# syspcb.net
KiCad netlist of a schematic drawn in Altium Designer
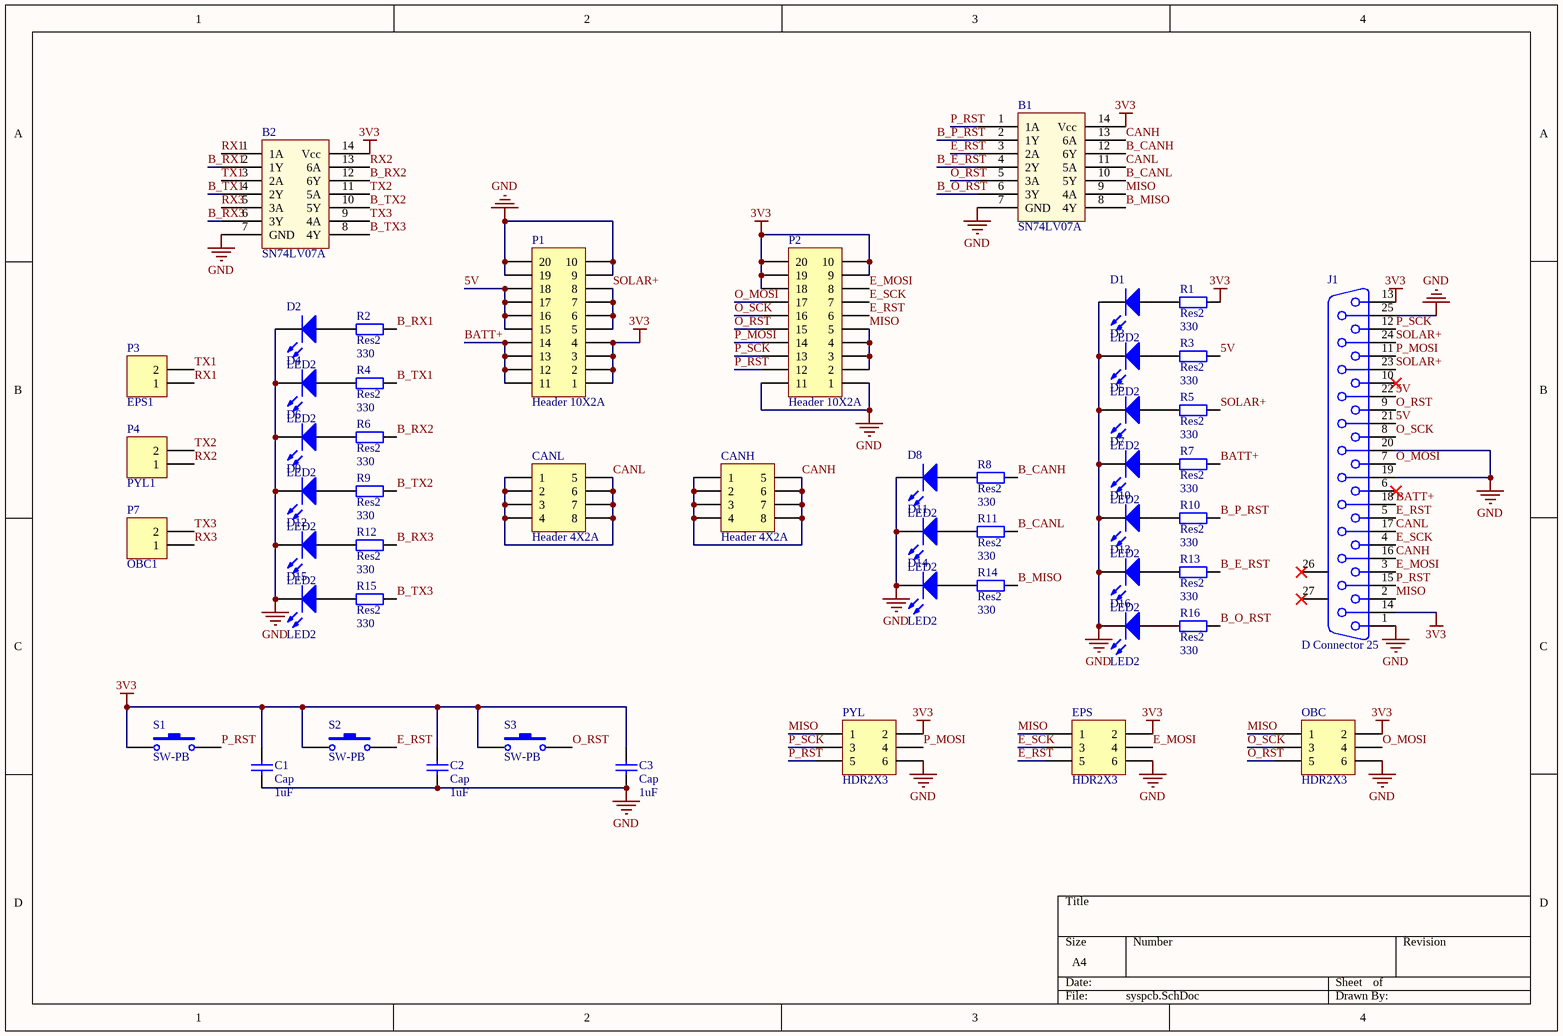
[diagram p0: syspcb.SchDoc]

(export (version "E")
  (design (tool "Eeschema 10.0.6"))
  (components
    (comp (ref "B1")
      (value "SN74LV07A")
      (footprint "SOIC127P600X175-14N")
      (libsource (lib "CUSTOM") (part "SN74LV07A"))
    )
    (comp (ref "B2")
      (value "SN74LV07A")
      (footprint "SOIC127P600X175-14N")
      (libsource (lib "CUSTOM") (part "SN74LV07A"))
    )
    (comp (ref "C1")
      (value "Cap")
      (footprint "1608[0603]")
      (description "Capacitor")
      (fields (field (name "ALTIUM_VALUE") "1uF") (field (name "PUBLISHER") "Altium Limited"))
      (libsource (lib "Miscellaneous Devices") (part "Cap"))
    )
    (comp (ref "C2")
      (value "Cap")
      (footprint "1608[0603]")
      (description "Capacitor")
      (fields (field (name "ALTIUM_VALUE") "1uF") (field (name "PUBLISHER") "Altium Limited"))
      (libsource (lib "Miscellaneous Devices") (part "Cap"))
    )
    (comp (ref "C3")
      (value "Cap")
      (footprint "1608[0603]")
      (description "Capacitor")
      (fields (field (name "ALTIUM_VALUE") "1uF") (field (name "PUBLISHER") "Altium Limited"))
      (libsource (lib "Miscellaneous Devices") (part "Cap"))
    )
    (comp (ref "CANH")
      (value "Header 4X2A")
      (footprint "HDR2X4_CEN")
      (description "Header, 4-Pin, Dual row")
      (fields (field (name "PUBLISHER") "Altium Limited"))
      (libsource (lib "Miscellaneous Connectors") (part "Header 4X2A"))
    )
    (comp (ref "CANL")
      (value "Header 4X2A")
      (footprint "HDR2X4_CEN")
      (description "Header, 4-Pin, Dual row")
      (fields (field (name "PUBLISHER") "Altium Limited"))
      (libsource (lib "Miscellaneous Connectors") (part "Header 4X2A"))
    )
    (comp (ref "D1")
      (value "LED2")
      (footprint "0603-LED")
      (description "Typical RED, GREEN, YELLOW, AMBER GaAs LED")
      (fields (field (name "PUBLISHER") "Altium Limited"))
      (libsource (lib "Miscellaneous Devices") (part "LED2"))
    )
    (comp (ref "D2")
      (value "LED2")
      (footprint "0603-LED")
      (description "Typical RED, GREEN, YELLOW, AMBER GaAs LED")
      (fields (field (name "PUBLISHER") "Altium Limited"))
      (libsource (lib "Miscellaneous Devices") (part "LED2"))
    )
    (comp (ref "D3")
      (value "LED2")
      (footprint "0603-LED")
      (description "Typical RED, GREEN, YELLOW, AMBER GaAs LED")
      (fields (field (name "PUBLISHER") "Altium Limited"))
      (libsource (lib "Miscellaneous Devices") (part "LED2"))
    )
    (comp (ref "D4")
      (value "LED2")
      (footprint "0603-LED")
      (description "Typical RED, GREEN, YELLOW, AMBER GaAs LED")
      (fields (field (name "PUBLISHER") "Altium Limited"))
      (libsource (lib "Miscellaneous Devices") (part "LED2"))
    )
    (comp (ref "D5")
      (value "LED2")
      (footprint "0603-LED")
      (description "Typical RED, GREEN, YELLOW, AMBER GaAs LED")
      (fields (field (name "PUBLISHER") "Altium Limited"))
      (libsource (lib "Miscellaneous Devices") (part "LED2"))
    )
    (comp (ref "D6")
      (value "LED2")
      (footprint "0603-LED")
      (description "Typical RED, GREEN, YELLOW, AMBER GaAs LED")
      (fields (field (name "PUBLISHER") "Altium Limited"))
      (libsource (lib "Miscellaneous Devices") (part "LED2"))
    )
    (comp (ref "D7")
      (value "LED2")
      (footprint "0603-LED")
      (description "Typical RED, GREEN, YELLOW, AMBER GaAs LED")
      (fields (field (name "PUBLISHER") "Altium Limited"))
      (libsource (lib "Miscellaneous Devices") (part "LED2"))
    )
    (comp (ref "D8")
      (value "LED2")
      (footprint "0603-LED")
      (description "Typical RED, GREEN, YELLOW, AMBER GaAs LED")
      (fields (field (name "PUBLISHER") "Altium Limited"))
      (libsource (lib "Miscellaneous Devices") (part "LED2"))
    )
    (comp (ref "D9")
      (value "LED2")
      (footprint "0603-LED")
      (description "Typical RED, GREEN, YELLOW, AMBER GaAs LED")
      (fields (field (name "PUBLISHER") "Altium Limited"))
      (libsource (lib "Miscellaneous Devices") (part "LED2"))
    )
    (comp (ref "D10")
      (value "LED2")
      (footprint "0603-LED")
      (description "Typical RED, GREEN, YELLOW, AMBER GaAs LED")
      (fields (field (name "PUBLISHER") "Altium Limited"))
      (libsource (lib "Miscellaneous Devices") (part "LED2"))
    )
    (comp (ref "D11")
      (value "LED2")
      (footprint "0603-LED")
      (description "Typical RED, GREEN, YELLOW, AMBER GaAs LED")
      (fields (field (name "PUBLISHER") "Altium Limited"))
      (libsource (lib "Miscellaneous Devices") (part "LED2"))
    )
    (comp (ref "D12")
      (value "LED2")
      (footprint "0603-LED")
      (description "Typical RED, GREEN, YELLOW, AMBER GaAs LED")
      (fields (field (name "PUBLISHER") "Altium Limited"))
      (libsource (lib "Miscellaneous Devices") (part "LED2"))
    )
    (comp (ref "D13")
      (value "LED2")
      (footprint "0603-LED")
      (description "Typical RED, GREEN, YELLOW, AMBER GaAs LED")
      (fields (field (name "PUBLISHER") "Altium Limited"))
      (libsource (lib "Miscellaneous Devices") (part "LED2"))
    )
    (comp (ref "D14")
      (value "LED2")
      (footprint "0603-LED")
      (description "Typical RED, GREEN, YELLOW, AMBER GaAs LED")
      (fields (field (name "PUBLISHER") "Altium Limited"))
      (libsource (lib "Miscellaneous Devices") (part "LED2"))
    )
    (comp (ref "D15")
      (value "LED2")
      (footprint "0603-LED")
      (description "Typical RED, GREEN, YELLOW, AMBER GaAs LED")
      (fields (field (name "PUBLISHER") "Altium Limited"))
      (libsource (lib "Miscellaneous Devices") (part "LED2"))
    )
    (comp (ref "D16")
      (value "LED2")
      (footprint "0603-LED")
      (description "Typical RED, GREEN, YELLOW, AMBER GaAs LED")
      (fields (field (name "PUBLISHER") "Altium Limited"))
      (libsource (lib "Miscellaneous Devices") (part "LED2"))
    )
    (comp (ref "EPS")
      (value "HDR2X3")
      (footprint "HDR2X3")
      (description "Header, 3-Pin, Dual row")
      (fields (field (name "PUBLISHER") "Altium Limited"))
      (libsource (lib "Miscellaneous Connectors") (part "MHDR2X3"))
    )
    (comp (ref "J1")
      (value "D Connector 25")
      (footprint "DSUB1.385-2H25A")
      (description "Receptacle Assembly, 25 Position, Right Angle")
      (fields (field (name "PUBLISHER") "Altium Limited"))
      (libsource (lib "Miscellaneous Connectors") (part "D Connector 25"))
    )
    (comp (ref "OBC")
      (value "HDR2X3")
      (footprint "HDR2X3")
      (description "Header, 3-Pin, Dual row")
      (fields (field (name "PUBLISHER") "Altium Limited"))
      (libsource (lib "Miscellaneous Connectors") (part "MHDR2X3"))
    )
    (comp (ref "P1")
      (value "Header 10X2A")
      (footprint "HDR2X10_CEN")
      (description "Header, 10-Pin, Dual row")
      (fields (field (name "PUBLISHER") "Altium Limited"))
      (libsource (lib "Miscellaneous Connectors") (part "Header 10X2A"))
    )
    (comp (ref "P2")
      (value "Header 10X2A")
      (footprint "HDR2X10_CEN")
      (description "Header, 10-Pin, Dual row")
      (fields (field (name "PUBLISHER") "Altium Limited"))
      (libsource (lib "Miscellaneous Connectors") (part "Header 10X2A"))
    )
    (comp (ref "P3")
      (value "EPS1")
      (footprint "HDR1X2")
      (description "Header, 2-Pin")
      (fields (field (name "PUBLISHER") "Altium Limited"))
      (libsource (lib "Miscellaneous Connectors") (part "Header 2"))
    )
    (comp (ref "P4")
      (value "PYL1")
      (footprint "HDR1X2")
      (description "Header, 2-Pin")
      (fields (field (name "PUBLISHER") "Altium Limited"))
      (libsource (lib "Miscellaneous Connectors") (part "Header 2"))
    )
    (comp (ref "P7")
      (value "OBC1")
      (footprint "HDR1X2")
      (description "Header, 2-Pin")
      (fields (field (name "PUBLISHER") "Altium Limited"))
      (libsource (lib "Miscellaneous Connectors") (part "Header 2"))
    )
    (comp (ref "PYL")
      (value "HDR2X3")
      (footprint "HDR2X3")
      (description "Header, 3-Pin, Dual row")
      (fields (field (name "PUBLISHER") "Altium Limited"))
      (libsource (lib "Miscellaneous Connectors") (part "MHDR2X3"))
    )
    (comp (ref "R1")
      (value "Res2")
      (footprint "J1-0603")
      (description "Resistor")
      (fields (field (name "ALTIUM_VALUE") "330") (field (name "PUBLISHER") "Altium Limited"))
      (libsource (lib "Miscellaneous Devices") (part "Res2"))
    )
    (comp (ref "R2")
      (value "Res2")
      (footprint "J1-0603")
      (description "Resistor")
      (fields (field (name "ALTIUM_VALUE") "330") (field (name "PUBLISHER") "Altium Limited"))
      (libsource (lib "Miscellaneous Devices") (part "Res2"))
    )
    (comp (ref "R3")
      (value "Res2")
      (footprint "J1-0603")
      (description "Resistor")
      (fields (field (name "ALTIUM_VALUE") "330") (field (name "PUBLISHER") "Altium Limited"))
      (libsource (lib "Miscellaneous Devices") (part "Res2"))
    )
    (comp (ref "R4")
      (value "Res2")
      (footprint "J1-0603")
      (description "Resistor")
      (fields (field (name "ALTIUM_VALUE") "330") (field (name "PUBLISHER") "Altium Limited"))
      (libsource (lib "Miscellaneous Devices") (part "Res2"))
    )
    (comp (ref "R5")
      (value "Res2")
      (footprint "J1-0603")
      (description "Resistor")
      (fields (field (name "ALTIUM_VALUE") "330") (field (name "PUBLISHER") "Altium Limited"))
      (libsource (lib "Miscellaneous Devices") (part "Res2"))
    )
    (comp (ref "R6")
      (value "Res2")
      (footprint "J1-0603")
      (description "Resistor")
      (fields (field (name "ALTIUM_VALUE") "330") (field (name "PUBLISHER") "Altium Limited"))
      (libsource (lib "Miscellaneous Devices") (part "Res2"))
    )
    (comp (ref "R7")
      (value "Res2")
      (footprint "J1-0603")
      (description "Resistor")
      (fields (field (name "ALTIUM_VALUE") "330") (field (name "PUBLISHER") "Altium Limited"))
      (libsource (lib "Miscellaneous Devices") (part "Res2"))
    )
    (comp (ref "R8")
      (value "Res2")
      (footprint "J1-0603")
      (description "Resistor")
      (fields (field (name "ALTIUM_VALUE") "330") (field (name "PUBLISHER") "Altium Limited"))
      (libsource (lib "Miscellaneous Devices") (part "Res2"))
    )
    (comp (ref "R9")
      (value "Res2")
      (footprint "J1-0603")
      (description "Resistor")
      (fields (field (name "ALTIUM_VALUE") "330") (field (name "PUBLISHER") "Altium Limited"))
      (libsource (lib "Miscellaneous Devices") (part "Res2"))
    )
    (comp (ref "R10")
      (value "Res2")
      (footprint "J1-0603")
      (description "Resistor")
      (fields (field (name "ALTIUM_VALUE") "330") (field (name "PUBLISHER") "Altium Limited"))
      (libsource (lib "Miscellaneous Devices") (part "Res2"))
    )
    (comp (ref "R11")
      (value "Res2")
      (footprint "J1-0603")
      (description "Resistor")
      (fields (field (name "ALTIUM_VALUE") "330") (field (name "PUBLISHER") "Altium Limited"))
      (libsource (lib "Miscellaneous Devices") (part "Res2"))
    )
    (comp (ref "R12")
      (value "Res2")
      (footprint "J1-0603")
      (description "Resistor")
      (fields (field (name "ALTIUM_VALUE") "330") (field (name "PUBLISHER") "Altium Limited"))
      (libsource (lib "Miscellaneous Devices") (part "Res2"))
    )
    (comp (ref "R13")
      (value "Res2")
      (footprint "J1-0603")
      (description "Resistor")
      (fields (field (name "ALTIUM_VALUE") "330") (field (name "PUBLISHER") "Altium Limited"))
      (libsource (lib "Miscellaneous Devices") (part "Res2"))
    )
    (comp (ref "R14")
      (value "Res2")
      (footprint "J1-0603")
      (description "Resistor")
      (fields (field (name "ALTIUM_VALUE") "330") (field (name "PUBLISHER") "Altium Limited"))
      (libsource (lib "Miscellaneous Devices") (part "Res2"))
    )
    (comp (ref "R15")
      (value "Res2")
      (footprint "J1-0603")
      (description "Resistor")
      (fields (field (name "ALTIUM_VALUE") "330") (field (name "PUBLISHER") "Altium Limited"))
      (libsource (lib "Miscellaneous Devices") (part "Res2"))
    )
    (comp (ref "R16")
      (value "Res2")
      (footprint "J1-0603")
      (description "Resistor")
      (fields (field (name "ALTIUM_VALUE") "330") (field (name "PUBLISHER") "Altium Limited"))
      (libsource (lib "Miscellaneous Devices") (part "Res2"))
    )
    (comp (ref "S1")
      (value "SW-PB")
      (footprint "SW_5-1437565-0")
      (description "Switch")
      (fields (field (name "PUBLISHER") "Altium Limited"))
      (libsource (lib "Miscellaneous Devices") (part "SW-PB"))
    )
    (comp (ref "S2")
      (value "SW-PB")
      (footprint "SW_5-1437565-0")
      (description "Switch")
      (fields (field (name "PUBLISHER") "Altium Limited"))
      (libsource (lib "Miscellaneous Devices") (part "SW-PB"))
    )
    (comp (ref "S3")
      (value "SW-PB")
      (footprint "SW_5-1437565-0")
      (description "Switch")
      (fields (field (name "PUBLISHER") "Altium Limited"))
      (libsource (lib "Miscellaneous Devices") (part "SW-PB"))
    )
  )
  (nets
    (net (code "1") (name "/5V") (class "Default")
      (node (ref "J1") (pin "21") (pinfunction "21_21") (pintype "passive"))
      (node (ref "J1") (pin "22") (pinfunction "22_22") (pintype "passive"))
      (node (ref "P1") (pin "15") (pinfunction "15_15") (pintype "passive"))
      (node (ref "P1") (pin "16") (pinfunction "16_16") (pintype "passive"))
      (node (ref "P1") (pin "17") (pinfunction "17_17") (pintype "passive"))
      (node (ref "P1") (pin "18") (pinfunction "18_18") (pintype "passive"))
      (node (ref "R3") (pin "1") (pinfunction "1_1") (pintype "passive"))
    )
    (net (code "2") (name "/BATT+") (class "Default")
      (node (ref "J1") (pin "18") (pinfunction "18_18") (pintype "passive"))
      (node (ref "P1") (pin "11") (pinfunction "11_11") (pintype "passive"))
      (node (ref "P1") (pin "12") (pinfunction "12_12") (pintype "passive"))
      (node (ref "P1") (pin "13") (pinfunction "13_13") (pintype "passive"))
      (node (ref "P1") (pin "14") (pinfunction "14_14") (pintype "passive"))
      (node (ref "R7") (pin "1") (pinfunction "1_1") (pintype "passive"))
    )
    (net (code "3") (name "/B_CANH") (class "Default")
      (node (ref "B1") (pin "12") (pinfunction "6Y_12") (pintype "passive"))
      (node (ref "R8") (pin "1") (pinfunction "1_1") (pintype "passive"))
    )
    (net (code "4") (name "/B_CANL") (class "Default")
      (node (ref "B1") (pin "10") (pinfunction "5Y_10") (pintype "passive"))
      (node (ref "R11") (pin "1") (pinfunction "1_1") (pintype "passive"))
    )
    (net (code "5") (name "/B_E_RST") (class "Default")
      (node (ref "B1") (pin "4") (pinfunction "2Y_4") (pintype "passive"))
      (node (ref "R13") (pin "1") (pinfunction "1_1") (pintype "passive"))
    )
    (net (code "6") (name "/B_MISO") (class "Default")
      (node (ref "B1") (pin "8") (pinfunction "4Y_8") (pintype "passive"))
      (node (ref "R14") (pin "1") (pinfunction "1_1") (pintype "passive"))
    )
    (net (code "7") (name "/B_O_RST") (class "Default")
      (node (ref "B1") (pin "6") (pinfunction "3Y_6") (pintype "passive"))
      (node (ref "R16") (pin "1") (pinfunction "1_1") (pintype "passive"))
    )
    (net (code "8") (name "/B_P_RST") (class "Default")
      (node (ref "B1") (pin "2") (pinfunction "1Y_2") (pintype "passive"))
      (node (ref "R10") (pin "1") (pinfunction "1_1") (pintype "passive"))
    )
    (net (code "9") (name "/B_RX1") (class "Default")
      (node (ref "B2") (pin "2") (pinfunction "1Y_2") (pintype "passive"))
      (node (ref "R2") (pin "1") (pinfunction "1_1") (pintype "passive"))
    )
    (net (code "10") (name "/B_RX2") (class "Default")
      (node (ref "B2") (pin "12") (pinfunction "6Y_12") (pintype "passive"))
      (node (ref "R6") (pin "1") (pinfunction "1_1") (pintype "passive"))
    )
    (net (code "11") (name "/B_RX3") (class "Default")
      (node (ref "B2") (pin "6") (pinfunction "3Y_6") (pintype "passive"))
      (node (ref "R12") (pin "1") (pinfunction "1_1") (pintype "passive"))
    )
    (net (code "12") (name "/B_TX1") (class "Default")
      (node (ref "B2") (pin "4") (pinfunction "2Y_4") (pintype "passive"))
      (node (ref "R4") (pin "1") (pinfunction "1_1") (pintype "passive"))
    )
    (net (code "13") (name "/B_TX2") (class "Default")
      (node (ref "B2") (pin "10") (pinfunction "5Y_10") (pintype "passive"))
      (node (ref "R9") (pin "1") (pinfunction "1_1") (pintype "passive"))
    )
    (net (code "14") (name "/B_TX3") (class "Default")
      (node (ref "B2") (pin "8") (pinfunction "4Y_8") (pintype "passive"))
      (node (ref "R15") (pin "1") (pinfunction "1_1") (pintype "passive"))
    )
    (net (code "15") (name "/CANH") (class "Default")
      (node (ref "B1") (pin "13") (pinfunction "6A_13") (pintype "passive"))
      (node (ref "CANH") (pin "1") (pinfunction "1_1") (pintype "passive"))
      (node (ref "CANH") (pin "2") (pinfunction "2_2") (pintype "passive"))
      (node (ref "CANH") (pin "3") (pinfunction "3_3") (pintype "passive"))
      (node (ref "CANH") (pin "4") (pinfunction "4_4") (pintype "passive"))
      (node (ref "CANH") (pin "5") (pinfunction "5_5") (pintype "passive"))
      (node (ref "CANH") (pin "6") (pinfunction "6_6") (pintype "passive"))
      (node (ref "CANH") (pin "7") (pinfunction "7_7") (pintype "passive"))
      (node (ref "CANH") (pin "8") (pinfunction "8_8") (pintype "passive"))
      (node (ref "J1") (pin "16") (pinfunction "16_16") (pintype "passive"))
    )
    (net (code "16") (name "/CANL") (class "Default")
      (node (ref "B1") (pin "11") (pinfunction "5A_11") (pintype "passive"))
      (node (ref "CANL") (pin "1") (pinfunction "1_1") (pintype "passive"))
      (node (ref "CANL") (pin "2") (pinfunction "2_2") (pintype "passive"))
      (node (ref "CANL") (pin "3") (pinfunction "3_3") (pintype "passive"))
      (node (ref "CANL") (pin "4") (pinfunction "4_4") (pintype "passive"))
      (node (ref "CANL") (pin "5") (pinfunction "5_5") (pintype "passive"))
      (node (ref "CANL") (pin "6") (pinfunction "6_6") (pintype "passive"))
      (node (ref "CANL") (pin "7") (pinfunction "7_7") (pintype "passive"))
      (node (ref "CANL") (pin "8") (pinfunction "8_8") (pintype "passive"))
      (node (ref "J1") (pin "17") (pinfunction "17_17") (pintype "passive"))
    )
    (net (code "17") (name "/E_MOSI") (class "Default")
      (node (ref "EPS") (pin "4") (pinfunction "4_4") (pintype "passive"))
      (node (ref "J1") (pin "3") (pinfunction "3_3") (pintype "passive"))
      (node (ref "P2") (pin "8") (pinfunction "8_8") (pintype "passive"))
    )
    (net (code "18") (name "/E_RST") (class "Default")
      (node (ref "B1") (pin "3") (pinfunction "2A_3") (pintype "passive"))
      (node (ref "EPS") (pin "5") (pinfunction "5_5") (pintype "passive"))
      (node (ref "J1") (pin "5") (pinfunction "5_5") (pintype "passive"))
      (node (ref "P2") (pin "6") (pinfunction "6_6") (pintype "passive"))
      (node (ref "S2") (pin "2") (pinfunction "2_2") (pintype "passive"))
    )
    (net (code "19") (name "/E_SCK") (class "Default")
      (node (ref "EPS") (pin "3") (pinfunction "3_3") (pintype "passive"))
      (node (ref "J1") (pin "4") (pinfunction "4_4") (pintype "passive"))
      (node (ref "P2") (pin "7") (pinfunction "7_7") (pintype "passive"))
    )
    (net (code "20") (name "/MISO") (class "Default")
      (node (ref "B1") (pin "9") (pinfunction "4A_9") (pintype "passive"))
      (node (ref "EPS") (pin "1") (pinfunction "1_1") (pintype "passive"))
      (node (ref "J1") (pin "2") (pinfunction "2_2") (pintype "passive"))
      (node (ref "OBC") (pin "1") (pinfunction "1_1") (pintype "passive"))
      (node (ref "P2") (pin "2") (pinfunction "2_2") (pintype "passive"))
      (node (ref "P2") (pin "3") (pinfunction "3_3") (pintype "passive"))
      (node (ref "P2") (pin "4") (pinfunction "4_4") (pintype "passive"))
      (node (ref "P2") (pin "5") (pinfunction "5_5") (pintype "passive"))
      (node (ref "PYL") (pin "1") (pinfunction "1_1") (pintype "passive"))
    )
    (net (code "21") (name "/O_MOSI") (class "Default")
      (node (ref "J1") (pin "7") (pinfunction "7_7") (pintype "passive"))
      (node (ref "OBC") (pin "4") (pinfunction "4_4") (pintype "passive"))
      (node (ref "P2") (pin "17") (pinfunction "17_17") (pintype "passive"))
    )
    (net (code "22") (name "/O_RST") (class "Default")
      (node (ref "B1") (pin "5") (pinfunction "3A_5") (pintype "passive"))
      (node (ref "J1") (pin "9") (pinfunction "9_9") (pintype "passive"))
      (node (ref "OBC") (pin "5") (pinfunction "5_5") (pintype "passive"))
      (node (ref "P2") (pin "15") (pinfunction "15_15") (pintype "passive"))
      (node (ref "S3") (pin "2") (pinfunction "2_2") (pintype "passive"))
    )
    (net (code "23") (name "/O_SCK") (class "Default")
      (node (ref "J1") (pin "8") (pinfunction "8_8") (pintype "passive"))
      (node (ref "OBC") (pin "3") (pinfunction "3_3") (pintype "passive"))
      (node (ref "P2") (pin "16") (pinfunction "16_16") (pintype "passive"))
    )
    (net (code "24") (name "/P_MOSI") (class "Default")
      (node (ref "J1") (pin "11") (pinfunction "11_11") (pintype "passive"))
      (node (ref "P2") (pin "14") (pinfunction "14_14") (pintype "passive"))
      (node (ref "PYL") (pin "4") (pinfunction "4_4") (pintype "passive"))
    )
    (net (code "25") (name "/P_RST") (class "Default")
      (node (ref "B1") (pin "1") (pinfunction "1A_1") (pintype "passive"))
      (node (ref "J1") (pin "15") (pinfunction "15_15") (pintype "passive"))
      (node (ref "P2") (pin "12") (pinfunction "12_12") (pintype "passive"))
      (node (ref "PYL") (pin "5") (pinfunction "5_5") (pintype "passive"))
      (node (ref "S1") (pin "2") (pinfunction "2_2") (pintype "passive"))
    )
    (net (code "26") (name "/P_SCK") (class "Default")
      (node (ref "J1") (pin "12") (pinfunction "12_12") (pintype "passive"))
      (node (ref "P2") (pin "13") (pinfunction "13_13") (pintype "passive"))
      (node (ref "PYL") (pin "3") (pinfunction "3_3") (pintype "passive"))
    )
    (net (code "27") (name "/RX1") (class "Default")
      (node (ref "B2") (pin "1") (pinfunction "1A_1") (pintype "passive"))
      (node (ref "P3") (pin "1") (pinfunction "1_1") (pintype "passive"))
    )
    (net (code "28") (name "/RX2") (class "Default")
      (node (ref "B2") (pin "13") (pinfunction "6A_13") (pintype "passive"))
      (node (ref "P4") (pin "1") (pinfunction "1_1") (pintype "passive"))
    )
    (net (code "29") (name "/RX3") (class "Default")
      (node (ref "B2") (pin "5") (pinfunction "3A_5") (pintype "passive"))
      (node (ref "P7") (pin "1") (pinfunction "1_1") (pintype "passive"))
    )
    (net (code "30") (name "/SOLAR+") (class "Default")
      (node (ref "J1") (pin "23") (pinfunction "23_23") (pintype "passive"))
      (node (ref "J1") (pin "24") (pinfunction "24_24") (pintype "passive"))
      (node (ref "P1") (pin "5") (pinfunction "5_5") (pintype "passive"))
      (node (ref "P1") (pin "6") (pinfunction "6_6") (pintype "passive"))
      (node (ref "P1") (pin "7") (pinfunction "7_7") (pintype "passive"))
      (node (ref "P1") (pin "8") (pinfunction "8_8") (pintype "passive"))
      (node (ref "R5") (pin "1") (pinfunction "1_1") (pintype "passive"))
    )
    (net (code "31") (name "/TX1") (class "Default")
      (node (ref "B2") (pin "3") (pinfunction "2A_3") (pintype "passive"))
      (node (ref "P3") (pin "2") (pinfunction "2_2") (pintype "passive"))
    )
    (net (code "32") (name "/TX2") (class "Default")
      (node (ref "B2") (pin "11") (pinfunction "5A_11") (pintype "passive"))
      (node (ref "P4") (pin "2") (pinfunction "2_2") (pintype "passive"))
    )
    (net (code "33") (name "/TX3") (class "Default")
      (node (ref "B2") (pin "9") (pinfunction "4A_9") (pintype "passive"))
      (node (ref "P7") (pin "2") (pinfunction "2_2") (pintype "passive"))
    )
    (net (code "34") (name "3V3") (class "Default")
      (node (ref "B1") (pin "14") (pinfunction "Vcc_14") (pintype "passive"))
      (node (ref "B2") (pin "14") (pinfunction "Vcc_14") (pintype "passive"))
      (node (ref "C1") (pin "2") (pinfunction "2_2") (pintype "passive"))
      (node (ref "C2") (pin "2") (pinfunction "2_2") (pintype "passive"))
      (node (ref "C3") (pin "2") (pinfunction "2_2") (pintype "passive"))
      (node (ref "EPS") (pin "2") (pinfunction "2_2") (pintype "passive"))
      (node (ref "J1") (pin "13") (pinfunction "13_13") (pintype "passive"))
      (node (ref "J1") (pin "14") (pinfunction "14_14") (pintype "passive"))
      (node (ref "OBC") (pin "2") (pinfunction "2_2") (pintype "passive"))
      (node (ref "P1") (pin "1") (pinfunction "1_1") (pintype "passive"))
      (node (ref "P1") (pin "2") (pinfunction "2_2") (pintype "passive"))
      (node (ref "P1") (pin "3") (pinfunction "3_3") (pintype "passive"))
      (node (ref "P1") (pin "4") (pinfunction "4_4") (pintype "passive"))
      (node (ref "P2") (pin "10") (pinfunction "10_10") (pintype "passive"))
      (node (ref "P2") (pin "18") (pinfunction "18_18") (pintype "passive"))
      (node (ref "P2") (pin "19") (pinfunction "19_19") (pintype "passive"))
      (node (ref "P2") (pin "20") (pinfunction "20_20") (pintype "passive"))
      (node (ref "P2") (pin "9") (pinfunction "9_9") (pintype "passive"))
      (node (ref "PYL") (pin "2") (pinfunction "2_2") (pintype "passive"))
      (node (ref "R1") (pin "1") (pinfunction "1_1") (pintype "passive"))
      (node (ref "S1") (pin "1") (pinfunction "1_1") (pintype "passive"))
      (node (ref "S2") (pin "1") (pinfunction "1_1") (pintype "passive"))
      (node (ref "S3") (pin "1") (pinfunction "1_1") (pintype "passive"))
    )
    (net (code "35") (name "GND") (class "Default")
      (node (ref "B1") (pin "7") (pinfunction "GND_7") (pintype "power_in"))
      (node (ref "B2") (pin "7") (pinfunction "GND_7") (pintype "power_in"))
      (node (ref "C1") (pin "1") (pinfunction "1_1") (pintype "passive"))
      (node (ref "C2") (pin "1") (pinfunction "1_1") (pintype "passive"))
      (node (ref "C3") (pin "1") (pinfunction "1_1") (pintype "passive"))
      (node (ref "D1") (pin "2") (pinfunction "K_2") (pintype "passive"))
      (node (ref "D10") (pin "2") (pinfunction "K_2") (pintype "passive"))
      (node (ref "D11") (pin "2") (pinfunction "K_2") (pintype "passive"))
      (node (ref "D12") (pin "2") (pinfunction "K_2") (pintype "passive"))
      (node (ref "D13") (pin "2") (pinfunction "K_2") (pintype "passive"))
      (node (ref "D14") (pin "2") (pinfunction "K_2") (pintype "passive"))
      (node (ref "D15") (pin "2") (pinfunction "K_2") (pintype "passive"))
      (node (ref "D16") (pin "2") (pinfunction "K_2") (pintype "passive"))
      (node (ref "D2") (pin "2") (pinfunction "K_2") (pintype "passive"))
      (node (ref "D3") (pin "2") (pinfunction "K_2") (pintype "passive"))
      (node (ref "D4") (pin "2") (pinfunction "K_2") (pintype "passive"))
      (node (ref "D5") (pin "2") (pinfunction "K_2") (pintype "passive"))
      (node (ref "D6") (pin "2") (pinfunction "K_2") (pintype "passive"))
      (node (ref "D7") (pin "2") (pinfunction "K_2") (pintype "passive"))
      (node (ref "D8") (pin "2") (pinfunction "K_2") (pintype "passive"))
      (node (ref "D9") (pin "2") (pinfunction "K_2") (pintype "passive"))
      (node (ref "EPS") (pin "6") (pinfunction "6_6") (pintype "passive"))
      (node (ref "J1") (pin "1") (pinfunction "1_1") (pintype "passive"))
      (node (ref "J1") (pin "19") (pinfunction "19_19") (pintype "passive"))
      (node (ref "J1") (pin "20") (pinfunction "20_20") (pintype "passive"))
      (node (ref "J1") (pin "25") (pinfunction "25_25") (pintype "passive"))
      (node (ref "OBC") (pin "6") (pinfunction "6_6") (pintype "passive"))
      (node (ref "P1") (pin "10") (pinfunction "10_10") (pintype "passive"))
      (node (ref "P1") (pin "19") (pinfunction "19_19") (pintype "passive"))
      (node (ref "P1") (pin "20") (pinfunction "20_20") (pintype "passive"))
      (node (ref "P1") (pin "9") (pinfunction "9_9") (pintype "passive"))
      (node (ref "P2") (pin "1") (pinfunction "1_1") (pintype "passive"))
      (node (ref "P2") (pin "11") (pinfunction "11_11") (pintype "passive"))
      (node (ref "PYL") (pin "6") (pinfunction "6_6") (pintype "passive"))
    )
    (net (code "36") (name "Net-(D1-A)") (class "Default")
      (node (ref "D1") (pin "1") (pinfunction "A_1") (pintype "passive"))
      (node (ref "R1") (pin "2") (pinfunction "2_2") (pintype "passive"))
    )
    (net (code "37") (name "Net-(D2-A)") (class "Default")
      (node (ref "D2") (pin "1") (pinfunction "A_1") (pintype "passive"))
      (node (ref "R2") (pin "2") (pinfunction "2_2") (pintype "passive"))
    )
    (net (code "38") (name "Net-(D3-A)") (class "Default")
      (node (ref "D3") (pin "1") (pinfunction "A_1") (pintype "passive"))
      (node (ref "R3") (pin "2") (pinfunction "2_2") (pintype "passive"))
    )
    (net (code "39") (name "Net-(D4-A)") (class "Default")
      (node (ref "D4") (pin "1") (pinfunction "A_1") (pintype "passive"))
      (node (ref "R4") (pin "2") (pinfunction "2_2") (pintype "passive"))
    )
    (net (code "40") (name "Net-(D5-A)") (class "Default")
      (node (ref "D5") (pin "1") (pinfunction "A_1") (pintype "passive"))
      (node (ref "R5") (pin "2") (pinfunction "2_2") (pintype "passive"))
    )
    (net (code "41") (name "Net-(D6-A)") (class "Default")
      (node (ref "D6") (pin "1") (pinfunction "A_1") (pintype "passive"))
      (node (ref "R6") (pin "2") (pinfunction "2_2") (pintype "passive"))
    )
    (net (code "42") (name "Net-(D7-A)") (class "Default")
      (node (ref "D7") (pin "1") (pinfunction "A_1") (pintype "passive"))
      (node (ref "R7") (pin "2") (pinfunction "2_2") (pintype "passive"))
    )
    (net (code "43") (name "Net-(D8-A)") (class "Default")
      (node (ref "D8") (pin "1") (pinfunction "A_1") (pintype "passive"))
      (node (ref "R8") (pin "2") (pinfunction "2_2") (pintype "passive"))
    )
    (net (code "44") (name "Net-(D9-A)") (class "Default")
      (node (ref "D9") (pin "1") (pinfunction "A_1") (pintype "passive"))
      (node (ref "R9") (pin "2") (pinfunction "2_2") (pintype "passive"))
    )
    (net (code "45") (name "Net-(D10-A)") (class "Default")
      (node (ref "D10") (pin "1") (pinfunction "A_1") (pintype "passive"))
      (node (ref "R10") (pin "2") (pinfunction "2_2") (pintype "passive"))
    )
    (net (code "46") (name "Net-(D11-A)") (class "Default")
      (node (ref "D11") (pin "1") (pinfunction "A_1") (pintype "passive"))
      (node (ref "R11") (pin "2") (pinfunction "2_2") (pintype "passive"))
    )
    (net (code "47") (name "Net-(D12-A)") (class "Default")
      (node (ref "D12") (pin "1") (pinfunction "A_1") (pintype "passive"))
      (node (ref "R12") (pin "2") (pinfunction "2_2") (pintype "passive"))
    )
    (net (code "48") (name "Net-(D13-A)") (class "Default")
      (node (ref "D13") (pin "1") (pinfunction "A_1") (pintype "passive"))
      (node (ref "R13") (pin "2") (pinfunction "2_2") (pintype "passive"))
    )
    (net (code "49") (name "Net-(D14-A)") (class "Default")
      (node (ref "D14") (pin "1") (pinfunction "A_1") (pintype "passive"))
      (node (ref "R14") (pin "2") (pinfunction "2_2") (pintype "passive"))
    )
    (net (code "50") (name "Net-(D15-A)") (class "Default")
      (node (ref "D15") (pin "1") (pinfunction "A_1") (pintype "passive"))
      (node (ref "R15") (pin "2") (pinfunction "2_2") (pintype "passive"))
    )
    (net (code "51") (name "Net-(D16-A)") (class "Default")
      (node (ref "D16") (pin "1") (pinfunction "A_1") (pintype "passive"))
      (node (ref "R16") (pin "2") (pinfunction "2_2") (pintype "passive"))
    )
    (net (code "52") (name "unconnected-(J1-MH1-Pad26)") (class "Default")
      (node (ref "J1") (pin "26") (pinfunction "MH1_26") (pintype "passive+no_connect"))
    )
    (net (code "53") (name "unconnected-(J1-MH2-Pad27)") (class "Default")
      (node (ref "J1") (pin "27") (pinfunction "MH2_27") (pintype "passive+no_connect"))
    )
    (net (code "54") (name "unconnected-(J1-Pad6)") (class "Default")
      (node (ref "J1") (pin "6") (pinfunction "6_6") (pintype "passive+no_connect"))
    )
    (net (code "55") (name "unconnected-(J1-Pad10)") (class "Default")
      (node (ref "J1") (pin "10") (pinfunction "10_10") (pintype "passive+no_connect"))
    )
  )
)
